# LB_-_MainBoard.net
KiCad netlist of a schematic drawn in Altium Designer
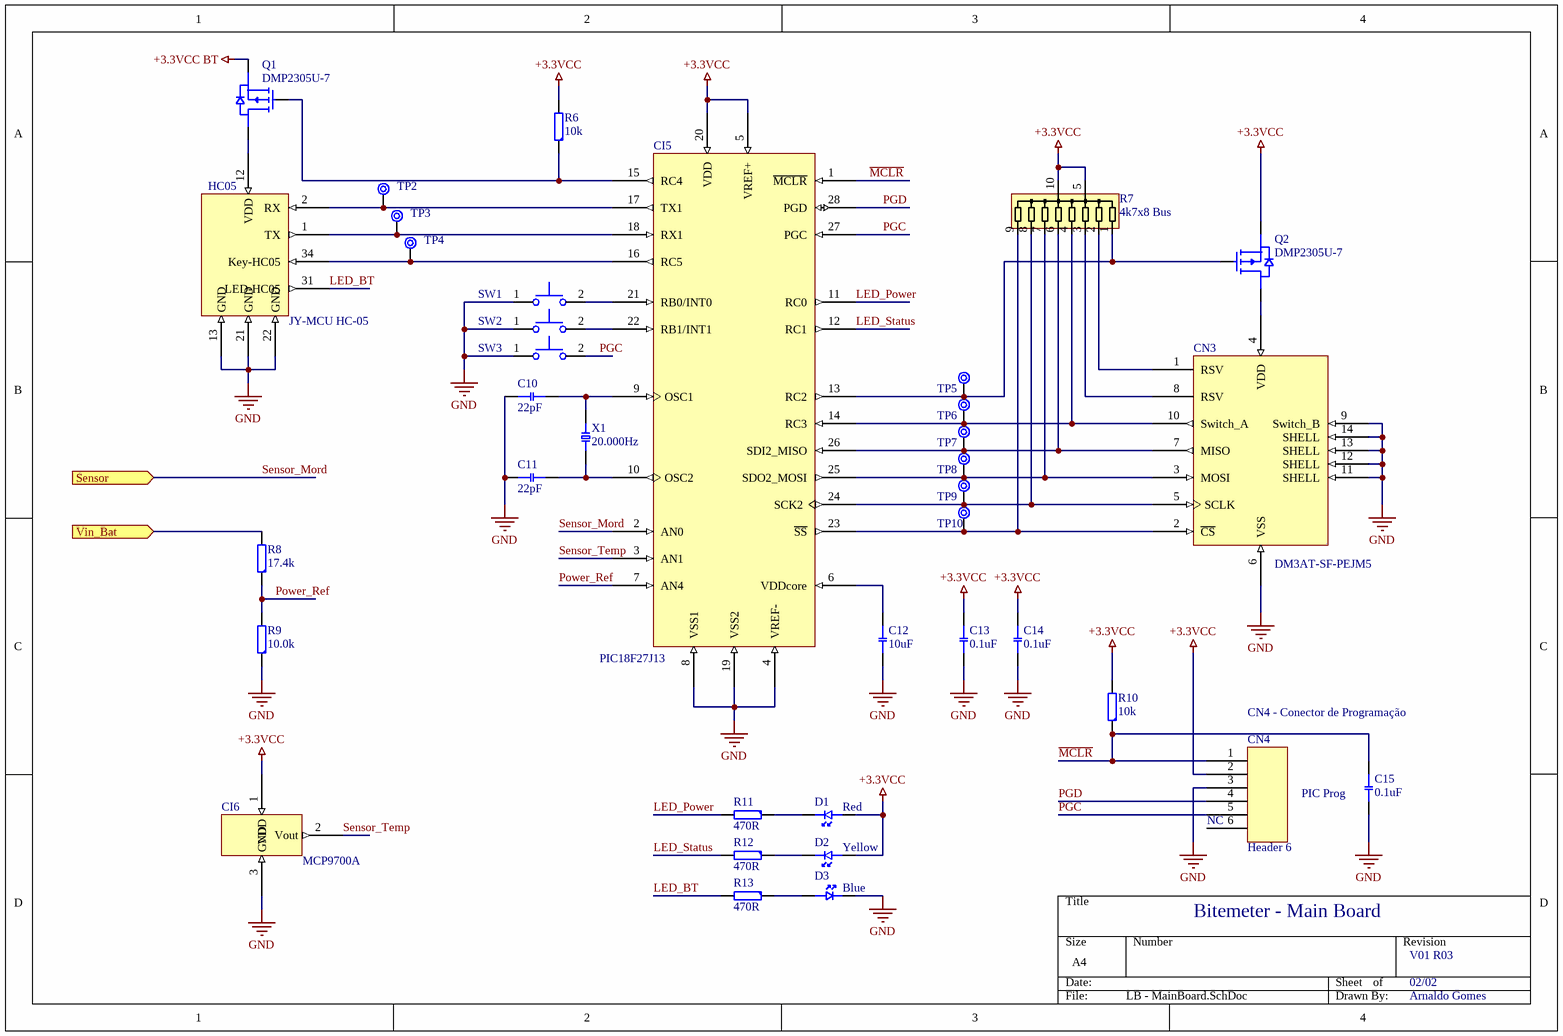
[diagram p0: LB - MainBoard.SchDoc]

(export (version "E")
  (design (tool "Eeschema 10.0.6"))
  (components
    (comp (ref "C10")
      (value "22pF")
      (footprint "R0805")
      (description "Capacitor 22pF")
      (libsource (lib "LB - V01-R01") (part "C"))
    )
    (comp (ref "C11")
      (value "22pF")
      (footprint "R0805")
      (description "Capacitor 22pF")
      (libsource (lib "LB - V01-R01") (part "C"))
    )
    (comp (ref "C12")
      (value "10uF")
      (footprint "R0805")
      (description "Capacitor 10uFx6.3V")
      (libsource (lib "LB - V01-R01") (part "C"))
    )
    (comp (ref "C13")
      (value "0.1uF")
      (footprint "R0805")
      (description "Capacitor 0.1uFx25V")
      (libsource (lib "LB - V01-R01") (part "C"))
    )
    (comp (ref "C14")
      (value "0.1uF")
      (footprint "R0805")
      (description "Capacitor 0.1uFx25V")
      (libsource (lib "LB - V01-R01") (part "C"))
    )
    (comp (ref "C15")
      (value "0.1uF")
      (footprint "R0805")
      (description "Capacitor 0.1uFx25V")
      (libsource (lib "LB - V01-R01") (part "C"))
    )
    (comp (ref "CI5")
      (value "PIC18F27J13")
      (footprint "PIC24F16KL402")
      (description "PIC18 8Bits")
      (libsource (lib "LB - V01-R01") (part "PIC18F27J13"))
    )
    (comp (ref "CI6")
      (value "MCP9700A")
      (footprint "MCP9700A")
      (description "Sensor de temperatura")
      (libsource (lib "LB - V01-R01") (part "MCP9700A"))
    )
    (comp (ref "CN3")
      (value "DM3AT-SF-PEJM5")
      (footprint "DM3AT")
      (description "Slot Micro SD - Push-Pull")
      (libsource (lib "LB - V01-R01") (part "MicroSD - DM3CS-SF"))
    )
    (comp (ref "CN4")
      (value "Header 6")
      (footprint "HDR1X6")
      (description "Header, 6-Pin")
      (libsource (lib "LB - V01-R01") (part "Conector Programação"))
    )
    (comp (ref "D1")
      (value "Red")
      (footprint "LTST-C930")
      (description "LED")
      (libsource (lib "LB - V01-R01") (part "LED"))
    )
    (comp (ref "D2")
      (value "Yellow")
      (footprint "LTST-C930")
      (description "LED")
      (libsource (lib "LB - V01-R01") (part "LED"))
    )
    (comp (ref "D3")
      (value "Blue")
      (footprint "LTST-C930")
      (description "LED")
      (libsource (lib "LB - V01-R01") (part "LED"))
    )
    (comp (ref "HC05")
      (value "JY-MCU HC-05")
      (footprint "JY-MCU HC-05")
      (description "Modulo Bluetooth HC-05")
      (libsource (lib "LB - V01-R01") (part "JY-MCU HC-05"))
    )
    (comp (ref "Q1")
      (value "DMP2305U-7")
      (footprint "DMP2305U-7")
      (description "MOSFET-P")
      (libsource (lib "LB - V01-R01") (part "MOSFET-P DIODE"))
    )
    (comp (ref "Q2")
      (value "DMP2305U-7")
      (footprint "DMP2305U-7")
      (description "MOSFET-P")
      (libsource (lib "PCB1301-R00C") (part "MOSFET-P DIODE"))
    )
    (comp (ref "R6") (value "10k") (footprint "R0805") (libsource (lib "LB - V01-R01") (part "R")))
    (comp (ref "R7")
      (value "4k7x8 Bus")
      (footprint "MMR15 Mod")
      (description "Brigde 4k7x8")
      (libsource (lib "LB - V01-R01") (part "R ARRAY BUS 8 - 10 PIN"))
    )
    (comp (ref "R8") (value "17.4k") (footprint "R0805") (libsource (lib "LB - V01-R01") (part "R")))
    (comp (ref "R9") (value "10.0k") (footprint "R0805") (libsource (lib "LB - V01-R01") (part "R")))
    (comp (ref "R10") (value "10k") (footprint "R0805") (libsource (lib "LB - V01-R01") (part "R")))
    (comp (ref "R11") (value "470R") (footprint "R0805") (libsource (lib "LB - V01-R01") (part "R")))
    (comp (ref "R12") (value "470R") (footprint "R0805") (libsource (lib "LB - V01-R01") (part "R")))
    (comp (ref "R13") (value "470R") (footprint "R0805") (libsource (lib "LB - V01-R01") (part "R")))
    (comp (ref "SW1")
      (value "~")
      (footprint "Push Button2")
      (description "Push Button")
      (libsource (lib "LB - V01-R01") (part "Push button"))
    )
    (comp (ref "SW2")
      (value "~")
      (footprint "Push Button2")
      (description "Push Button")
      (libsource (lib "LB - V01-R01") (part "Push button"))
    )
    (comp (ref "SW3")
      (value "~")
      (footprint "Push Button2")
      (description "Push Button")
      (libsource (lib "LB - V01-R01") (part "Push button"))
    )
    (comp (ref "TP2")
      (value "TP")
      (footprint "TPSMD")
      (description "Test Point")
      (libsource (lib "LB - V01-R01") (part "TP"))
    )
    (comp (ref "TP3")
      (value "TP")
      (footprint "TPSMD")
      (description "Test Point")
      (libsource (lib "LB - V01-R01") (part "TP"))
    )
    (comp (ref "TP4")
      (value "TP")
      (footprint "TPSMD")
      (description "Test Point")
      (libsource (lib "LB - V01-R01") (part "TP"))
    )
    (comp (ref "TP5")
      (value "TP")
      (footprint "TPSMD")
      (description "Test Point")
      (libsource (lib "LB - V01-R01") (part "TP"))
    )
    (comp (ref "TP6")
      (value "TP")
      (footprint "TPSMD")
      (description "Test Point")
      (libsource (lib "LB - V01-R01") (part "TP"))
    )
    (comp (ref "TP7")
      (value "TP")
      (footprint "TPSMD")
      (description "Test Point")
      (libsource (lib "LB - V01-R01") (part "TP"))
    )
    (comp (ref "TP8")
      (value "TP")
      (footprint "TPSMD")
      (description "Test Point")
      (libsource (lib "LB - V01-R01") (part "TP"))
    )
    (comp (ref "TP9")
      (value "TP")
      (footprint "TPSMD")
      (description "Test Point")
      (libsource (lib "LB - V01-R01") (part "TP"))
    )
    (comp (ref "TP10")
      (value "TP")
      (footprint "TPSMD")
      (description "Test Point")
      (libsource (lib "LB - V01-R01") (part "TP"))
    )
    (comp (ref "X1")
      (value "20.000Hz")
      (footprint "ABM3")
      (description "Crystal 20.000Hz")
      (libsource (lib "LB - V01-R01") (part "XTAL"))
    )
  )
  (nets
    (net (code "1") (name "+3.3VCC") (class "Default")
      (node (ref "C13") (pin "2") (pinfunction "B_2") (pintype "passive"))
      (node (ref "C14") (pin "2") (pinfunction "B_2") (pintype "passive"))
      (node (ref "CI5") (pin "20") (pinfunction "VDD_20") (pintype "input"))
      (node (ref "CI5") (pin "5") (pinfunction "VREF+_5") (pintype "input"))
      (node (ref "CI6") (pin "1") (pinfunction "VDD_1") (pintype "input"))
      (node (ref "CN4") (pin "2") (pinfunction "2_2") (pintype "passive"))
      (node (ref "D1") (pin "A") (pinfunction "A_A") (pintype "passive"))
      (node (ref "D2") (pin "A") (pinfunction "A_A") (pintype "passive"))
      (node (ref "Q2") (pin "S") (pinfunction "S_S") (pintype "passive"))
      (node (ref "R10") (pin "2") (pinfunction "B_2") (pintype "passive"))
      (node (ref "R6") (pin "2") (pinfunction "B_2") (pintype "passive"))
      (node (ref "R7") (pin "10") (pinfunction "10_10") (pintype "passive"))
      (node (ref "R7") (pin "5") (pintype "passive"))
    )
    (net (code "2") (name "+3.3VCC BT") (class "Default")
      (node (ref "Q1") (pin "S") (pinfunction "S_S") (pintype "passive"))
    )
    (net (code "3") (name "/LED_BT") (class "Default")
      (node (ref "HC05") (pin "31") (pinfunction "LED-HC05_31") (pintype "output"))
      (node (ref "R13") (pin "2") (pinfunction "B_2") (pintype "passive"))
    )
    (net (code "4") (name "/LED_Power") (class "Default")
      (node (ref "CI5") (pin "11") (pinfunction "RC0_11") (pintype "output"))
      (node (ref "R11") (pin "2") (pinfunction "B_2") (pintype "passive"))
    )
    (net (code "5") (name "/LED_Status") (class "Default")
      (node (ref "CI5") (pin "12") (pinfunction "RC1_12") (pintype "output"))
      (node (ref "R12") (pin "2") (pinfunction "B_2") (pintype "passive"))
    )
    (net (code "6") (name "/PGC") (class "Default")
      (node (ref "CI5") (pin "27") (pinfunction "PGC_27") (pintype "input"))
      (node (ref "CN4") (pin "5") (pinfunction "5_5") (pintype "passive"))
      (node (ref "SW3") (pin "2") (pinfunction "2_2") (pintype "passive"))
    )
    (net (code "7") (name "/PGD") (class "Default")
      (node (ref "CI5") (pin "28") (pinfunction "PGD_28") (pintype "bidirectional"))
      (node (ref "CN4") (pin "4") (pinfunction "4_4") (pintype "passive"))
    )
    (net (code "8") (name "/Power_Ref") (class "Default")
      (node (ref "CI5") (pin "7") (pinfunction "AN4_7") (pintype "input"))
      (node (ref "R8") (pin "1") (pinfunction "A_1") (pintype "passive"))
      (node (ref "R9") (pin "2") (pinfunction "B_2") (pintype "passive"))
    )
    (net (code "9") (name "/Sensor_Mord") (class "Default")
      (node (ref "CI5") (pin "2") (pinfunction "AN0_2") (pintype "input"))
    )
    (net (code "10") (name "/Sensor_Temp") (class "Default")
      (node (ref "CI5") (pin "3") (pinfunction "AN1_3") (pintype "input"))
      (node (ref "CI6") (pin "2") (pinfunction "Vout_2") (pintype "output"))
    )
    (net (code "11") (name "/Vin_Bat") (class "Default")
      (node (ref "R8") (pin "2") (pinfunction "B_2") (pintype "passive"))
    )
    (net (code "12") (name "/~{MCLR}") (class "Default")
      (node (ref "C15") (pin "2") (pinfunction "B_2") (pintype "passive"))
      (node (ref "CI5") (pin "1") (pinfunction "~{MCLR}_1") (pintype "input"))
      (node (ref "CN4") (pin "1") (pinfunction "1_1") (pintype "passive"))
      (node (ref "R10") (pin "1") (pinfunction "A_1") (pintype "passive"))
    )
    (net (code "13") (name "GND") (class "Default")
      (node (ref "C10") (pin "2") (pinfunction "B_2") (pintype "passive"))
      (node (ref "C11") (pin "2") (pinfunction "B_2") (pintype "passive"))
      (node (ref "C12") (pin "1") (pinfunction "A_1") (pintype "passive"))
      (node (ref "C13") (pin "1") (pinfunction "A_1") (pintype "passive"))
      (node (ref "C14") (pin "1") (pinfunction "A_1") (pintype "passive"))
      (node (ref "C15") (pin "1") (pinfunction "A_1") (pintype "passive"))
      (node (ref "CI5") (pin "19") (pinfunction "VSS2_19") (pintype "input"))
      (node (ref "CI5") (pin "4") (pinfunction "VREF-_4") (pintype "input"))
      (node (ref "CI5") (pin "8") (pinfunction "VSS1_8") (pintype "input"))
      (node (ref "CI6") (pin "3") (pinfunction "GND_3") (pintype "input"))
      (node (ref "CN3") (pin "11") (pinfunction "SHELL_11") (pintype "input"))
      (node (ref "CN3") (pin "12") (pinfunction "SHELL_12") (pintype "input"))
      (node (ref "CN3") (pin "13") (pinfunction "SHELL_13") (pintype "input"))
      (node (ref "CN3") (pin "14") (pinfunction "SHELL_14") (pintype "input"))
      (node (ref "CN3") (pin "6") (pinfunction "VSS_6") (pintype "input"))
      (node (ref "CN3") (pin "9") (pinfunction "Switch_B_9") (pintype "input"))
      (node (ref "CN4") (pin "3") (pinfunction "3_3") (pintype "passive"))
      (node (ref "D3") (pin "K") (pinfunction "K_K") (pintype "passive"))
      (node (ref "HC05") (pin "13") (pinfunction "GND_13") (pintype "input"))
      (node (ref "HC05") (pin "21") (pinfunction "GND_21") (pintype "input"))
      (node (ref "HC05") (pin "22") (pinfunction "GND_22") (pintype "input"))
      (node (ref "R9") (pin "1") (pinfunction "A_1") (pintype "passive"))
      (node (ref "SW1") (pin "1") (pinfunction "1_1") (pintype "passive"))
      (node (ref "SW2") (pin "1") (pinfunction "1_1") (pintype "passive"))
      (node (ref "SW3") (pin "1") (pinfunction "1_1") (pintype "passive"))
    )
    (net (code "14") (name "Net-(C10-A)") (class "Default")
      (node (ref "C10") (pin "1") (pinfunction "A_1") (pintype "passive"))
      (node (ref "CI5") (pin "9") (pinfunction "OSC1_9") (pintype "input"))
      (node (ref "X1") (pin "1") (pinfunction "A_1") (pintype "passive"))
    )
    (net (code "15") (name "Net-(C11-A)") (class "Default")
      (node (ref "C11") (pin "1") (pinfunction "A_1") (pintype "passive"))
      (node (ref "CI5") (pin "10") (pinfunction "OSC2_10") (pintype "output"))
      (node (ref "X1") (pin "2") (pinfunction "B_2") (pintype "passive"))
    )
    (net (code "16") (name "Net-(C12-B)") (class "Default")
      (node (ref "C12") (pin "2") (pinfunction "B_2") (pintype "passive"))
      (node (ref "CI5") (pin "6") (pinfunction "VDDcore_6") (pintype "input"))
    )
    (net (code "17") (name "Net-(CI5-RB0{slash}INT0)") (class "Default")
      (node (ref "CI5") (pin "21") (pinfunction "RB0/INT0_21") (pintype "input"))
      (node (ref "SW1") (pin "2") (pinfunction "2_2") (pintype "passive"))
    )
    (net (code "18") (name "Net-(CI5-RB1{slash}INT1)") (class "Default")
      (node (ref "CI5") (pin "22") (pinfunction "RB1/INT1_22") (pintype "input"))
      (node (ref "SW2") (pin "2") (pinfunction "2_2") (pintype "passive"))
    )
    (net (code "19") (name "Net-(CI5-RC2)") (class "Default")
      (node (ref "CI5") (pin "13") (pinfunction "RC2_13") (pintype "output"))
      (node (ref "Q2") (pin "G") (pinfunction "G_G") (pintype "passive"))
      (node (ref "R7") (pin "1") (pintype "passive"))
      (node (ref "TP5") (pin "1") (pinfunction "1_1") (pintype "passive"))
    )
    (net (code "20") (name "Net-(CI5-RC3)") (class "Default")
      (node (ref "CI5") (pin "14") (pinfunction "RC3_14") (pintype "input"))
      (node (ref "CN3") (pin "10") (pinfunction "Switch_A_10") (pintype "output"))
      (node (ref "R7") (pin "4") (pintype "passive"))
      (node (ref "TP6") (pin "1") (pinfunction "1_1") (pintype "passive"))
    )
    (net (code "21") (name "Net-(CI5-RC4)") (class "Default")
      (node (ref "CI5") (pin "15") (pinfunction "RC4_15") (pintype "output"))
      (node (ref "Q1") (pin "G") (pinfunction "G_G") (pintype "passive"))
      (node (ref "R6") (pin "1") (pinfunction "A_1") (pintype "passive"))
    )
    (net (code "22") (name "Net-(CI5-RC5)") (class "Default")
      (node (ref "CI5") (pin "16") (pinfunction "RC5_16") (pintype "output"))
      (node (ref "HC05") (pin "34") (pinfunction "Key-HC05_34") (pintype "input"))
      (node (ref "TP4") (pin "1") (pinfunction "1_1") (pintype "passive"))
    )
    (net (code "23") (name "Net-(CI5-RX1)") (class "Default")
      (node (ref "CI5") (pin "18") (pinfunction "RX1_18") (pintype "input"))
      (node (ref "HC05") (pin "1") (pinfunction "TX_1") (pintype "output"))
      (node (ref "TP3") (pin "1") (pinfunction "1_1") (pintype "passive"))
    )
    (net (code "24") (name "Net-(CI5-SCK2)") (class "Default")
      (node (ref "CI5") (pin "24") (pinfunction "SCK2_24") (pintype "output"))
      (node (ref "CN3") (pin "5") (pinfunction "SCLK_5") (pintype "input"))
      (node (ref "R7") (pin "8") (pintype "passive"))
      (node (ref "TP9") (pin "1") (pinfunction "1_1") (pintype "passive"))
    )
    (net (code "25") (name "Net-(CI5-SDI2_MISO)") (class "Default")
      (node (ref "CI5") (pin "26") (pinfunction "SDI2_MISO_26") (pintype "input"))
      (node (ref "CN3") (pin "7") (pinfunction "MISO_7") (pintype "output"))
      (node (ref "R7") (pin "6") (pintype "passive"))
      (node (ref "TP7") (pin "1") (pinfunction "1_1") (pintype "passive"))
    )
    (net (code "26") (name "Net-(CI5-SDO2_MOSI)") (class "Default")
      (node (ref "CI5") (pin "25") (pinfunction "SDO2_MOSI_25") (pintype "output"))
      (node (ref "CN3") (pin "3") (pinfunction "MOSI_3") (pintype "input"))
      (node (ref "R7") (pin "7") (pintype "passive"))
      (node (ref "TP8") (pin "1") (pinfunction "1_1") (pintype "passive"))
    )
    (net (code "27") (name "Net-(CI5-TX1)") (class "Default")
      (node (ref "CI5") (pin "17") (pinfunction "TX1_17") (pintype "output"))
      (node (ref "HC05") (pin "2") (pinfunction "RX_2") (pintype "input"))
      (node (ref "TP2") (pin "1") (pinfunction "1_1") (pintype "passive"))
    )
    (net (code "28") (name "Net-(CI5-~{SS})") (class "Default")
      (node (ref "CI5") (pin "23") (pinfunction "~{SS}_23") (pintype "output"))
      (node (ref "CN3") (pin "2") (pinfunction "~{CS}_2") (pintype "input"))
      (node (ref "R7") (pin "9") (pinfunction "9_9") (pintype "passive"))
      (node (ref "TP10") (pin "1") (pinfunction "1_1") (pintype "passive"))
    )
    (net (code "29") (name "Net-(CN3-RSV-Pad1)") (class "Default")
      (node (ref "CN3") (pin "1") (pinfunction "RSV_1") (pintype "passive"))
      (node (ref "R7") (pin "2") (pintype "passive"))
    )
    (net (code "30") (name "Net-(CN3-RSV-Pad8)") (class "Default")
      (node (ref "CN3") (pin "8") (pinfunction "RSV_8") (pintype "passive"))
      (node (ref "R7") (pin "3") (pintype "passive"))
    )
    (net (code "31") (name "Net-(CN3-VDD)") (class "Default")
      (node (ref "CN3") (pin "4") (pinfunction "VDD_4") (pintype "input"))
      (node (ref "Q2") (pin "D") (pinfunction "D_D") (pintype "passive"))
    )
    (net (code "32") (name "Net-(HC05-VDD)") (class "Default")
      (node (ref "HC05") (pin "12") (pinfunction "VDD_12") (pintype "input"))
      (node (ref "Q1") (pin "D") (pinfunction "D_D") (pintype "passive"))
    )
    (net (code "33") (name "Net-(R11-A)") (class "Default")
      (node (ref "D1") (pin "K") (pinfunction "K_K") (pintype "passive"))
      (node (ref "R11") (pin "1") (pinfunction "A_1") (pintype "passive"))
    )
    (net (code "34") (name "Net-(R12-A)") (class "Default")
      (node (ref "D2") (pin "K") (pinfunction "K_K") (pintype "passive"))
      (node (ref "R12") (pin "1") (pinfunction "A_1") (pintype "passive"))
    )
    (net (code "35") (name "Net-(R13-A)") (class "Default")
      (node (ref "D3") (pin "A") (pinfunction "A_A") (pintype "passive"))
      (node (ref "R13") (pin "1") (pinfunction "A_1") (pintype "passive"))
    )
    (net (code "36") (name "unconnected-(CN4-Pad6)") (class "Default")
      (node (ref "CN4") (pin "6") (pinfunction "6_6") (pintype "passive"))
    )
  )
)
